# sensor.net
KiCad netlist of a schematic drawn in Altium Designer
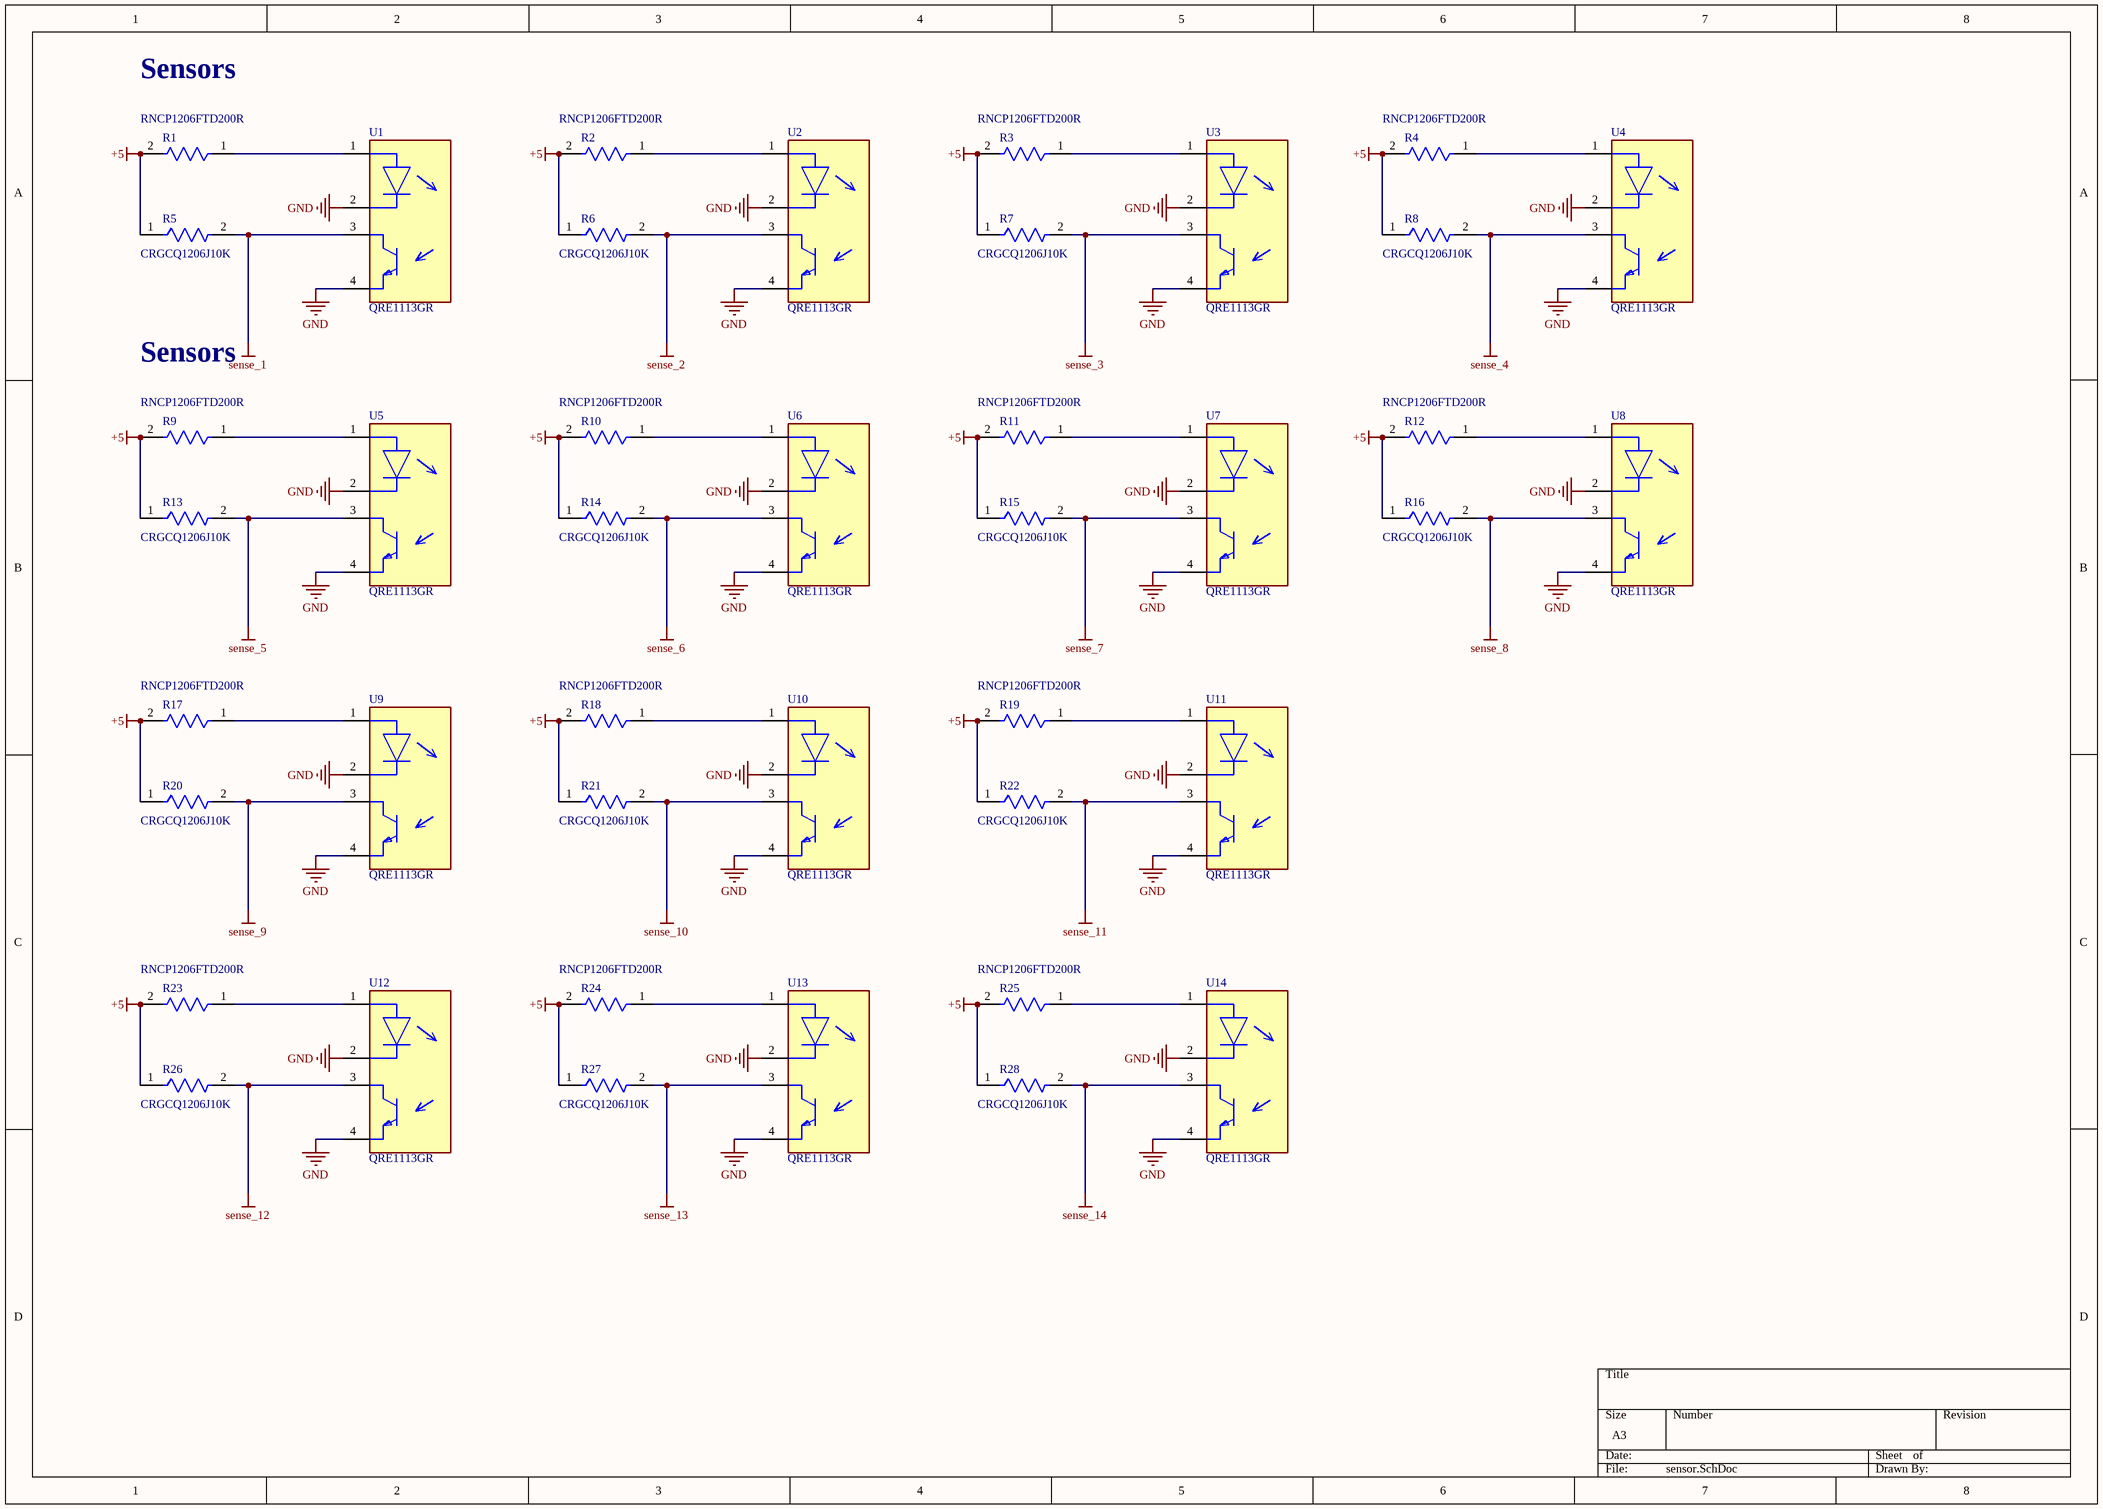
[diagram p0: sensor.SchDoc]

(export (version "E")
  (design (tool "Eeschema 10.0.6"))
  (components
    (comp (ref "R1")
      (value "RNCP1206FTD200R")
      (footprint "FP-RNCP1206-IPC_B")
      (description "200Ω ±1% 0.5W 1206 High Power Anti-Sulfur Thin Film Chip Resistor")
      (fields (field (name "TOLERANCE") "1%"))
      (libsource (lib "Altium Content Vault") (part "1029c3af85768c4190bb7ad29bc67b5"))
    )
    (comp (ref "R2")
      (value "RNCP1206FTD200R")
      (footprint "FP-RNCP1206-IPC_B")
      (description "200Ω ±1% 0.5W 1206 High Power Anti-Sulfur Thin Film Chip Resistor")
      (fields (field (name "TOLERANCE") "1%"))
      (libsource (lib "Altium Content Vault") (part "1029c3af85768c4190bb7ad29bc67b5"))
    )
    (comp (ref "R3")
      (value "RNCP1206FTD200R")
      (footprint "FP-RNCP1206-IPC_B")
      (description "200Ω ±1% 0.5W 1206 High Power Anti-Sulfur Thin Film Chip Resistor")
      (fields (field (name "TOLERANCE") "1%"))
      (libsource (lib "Altium Content Vault") (part "1029c3af85768c4190bb7ad29bc67b5"))
    )
    (comp (ref "R4")
      (value "RNCP1206FTD200R")
      (footprint "FP-RNCP1206-IPC_B")
      (description "200Ω ±1% 0.5W 1206 High Power Anti-Sulfur Thin Film Chip Resistor")
      (fields (field (name "TOLERANCE") "1%"))
      (libsource (lib "Altium Content Vault") (part "1029c3af85768c4190bb7ad29bc67b5"))
    )
    (comp (ref "R5")
      (value "CRGCQ1206J10K")
      (footprint "FP-CRGCQ1206-IPC_C")
      (description "CRGCQ1206 10KΩ 0.25W 5% ±100ppm/°C 200V")
      (fields (field (name "MANUFACTURER") "TE Connectivity") (field (name "TOLERANCE") "0.05"))
      (libsource (lib "Altium Content Vault") (part "1029c3af85768c4190bb7ad29bc67b5"))
    )
    (comp (ref "R6")
      (value "CRGCQ1206J10K")
      (footprint "FP-CRGCQ1206-IPC_C")
      (description "CRGCQ1206 10KΩ 0.25W 5% ±100ppm/°C 200V")
      (fields (field (name "MANUFACTURER") "TE Connectivity") (field (name "TOLERANCE") "0.05"))
      (libsource (lib "Altium Content Vault") (part "1029c3af85768c4190bb7ad29bc67b5"))
    )
    (comp (ref "R7")
      (value "CRGCQ1206J10K")
      (footprint "FP-CRGCQ1206-IPC_C")
      (description "CRGCQ1206 10KΩ 0.25W 5% ±100ppm/°C 200V")
      (fields (field (name "MANUFACTURER") "TE Connectivity") (field (name "TOLERANCE") "0.05"))
      (libsource (lib "Altium Content Vault") (part "1029c3af85768c4190bb7ad29bc67b5"))
    )
    (comp (ref "R8")
      (value "CRGCQ1206J10K")
      (footprint "FP-CRGCQ1206-IPC_C")
      (description "CRGCQ1206 10KΩ 0.25W 5% ±100ppm/°C 200V")
      (fields (field (name "MANUFACTURER") "TE Connectivity") (field (name "TOLERANCE") "0.05"))
      (libsource (lib "Altium Content Vault") (part "1029c3af85768c4190bb7ad29bc67b5"))
    )
    (comp (ref "R9")
      (value "RNCP1206FTD200R")
      (footprint "FP-RNCP1206-IPC_B")
      (description "200Ω ±1% 0.5W 1206 High Power Anti-Sulfur Thin Film Chip Resistor")
      (fields (field (name "TOLERANCE") "1%"))
      (libsource (lib "Altium Content Vault") (part "1029c3af85768c4190bb7ad29bc67b5"))
    )
    (comp (ref "R10")
      (value "RNCP1206FTD200R")
      (footprint "FP-RNCP1206-IPC_B")
      (description "200Ω ±1% 0.5W 1206 High Power Anti-Sulfur Thin Film Chip Resistor")
      (fields (field (name "TOLERANCE") "1%"))
      (libsource (lib "Altium Content Vault") (part "1029c3af85768c4190bb7ad29bc67b5"))
    )
    (comp (ref "R11")
      (value "RNCP1206FTD200R")
      (footprint "FP-RNCP1206-IPC_B")
      (description "200Ω ±1% 0.5W 1206 High Power Anti-Sulfur Thin Film Chip Resistor")
      (fields (field (name "TOLERANCE") "1%"))
      (libsource (lib "Altium Content Vault") (part "1029c3af85768c4190bb7ad29bc67b5"))
    )
    (comp (ref "R12")
      (value "RNCP1206FTD200R")
      (footprint "FP-RNCP1206-IPC_B")
      (description "200Ω ±1% 0.5W 1206 High Power Anti-Sulfur Thin Film Chip Resistor")
      (fields (field (name "TOLERANCE") "1%"))
      (libsource (lib "Altium Content Vault") (part "1029c3af85768c4190bb7ad29bc67b5"))
    )
    (comp (ref "R13")
      (value "CRGCQ1206J10K")
      (footprint "FP-CRGCQ1206-IPC_C")
      (description "CRGCQ1206 10KΩ 0.25W 5% ±100ppm/°C 200V")
      (fields (field (name "MANUFACTURER") "TE Connectivity") (field (name "TOLERANCE") "0.05"))
      (libsource (lib "Altium Content Vault") (part "1029c3af85768c4190bb7ad29bc67b5"))
    )
    (comp (ref "R14")
      (value "CRGCQ1206J10K")
      (footprint "FP-CRGCQ1206-IPC_C")
      (description "CRGCQ1206 10KΩ 0.25W 5% ±100ppm/°C 200V")
      (fields (field (name "MANUFACTURER") "TE Connectivity") (field (name "TOLERANCE") "0.05"))
      (libsource (lib "Altium Content Vault") (part "1029c3af85768c4190bb7ad29bc67b5"))
    )
    (comp (ref "R15")
      (value "CRGCQ1206J10K")
      (footprint "FP-CRGCQ1206-IPC_C")
      (description "CRGCQ1206 10KΩ 0.25W 5% ±100ppm/°C 200V")
      (fields (field (name "MANUFACTURER") "TE Connectivity") (field (name "TOLERANCE") "0.05"))
      (libsource (lib "Altium Content Vault") (part "1029c3af85768c4190bb7ad29bc67b5"))
    )
    (comp (ref "R16")
      (value "CRGCQ1206J10K")
      (footprint "FP-CRGCQ1206-IPC_C")
      (description "CRGCQ1206 10KΩ 0.25W 5% ±100ppm/°C 200V")
      (fields (field (name "MANUFACTURER") "TE Connectivity") (field (name "TOLERANCE") "0.05"))
      (libsource (lib "Altium Content Vault") (part "1029c3af85768c4190bb7ad29bc67b5"))
    )
    (comp (ref "R17")
      (value "RNCP1206FTD200R")
      (footprint "FP-RNCP1206-IPC_B")
      (description "200Ω ±1% 0.5W 1206 High Power Anti-Sulfur Thin Film Chip Resistor")
      (fields (field (name "TOLERANCE") "1%"))
      (libsource (lib "Altium Content Vault") (part "1029c3af85768c4190bb7ad29bc67b5"))
    )
    (comp (ref "R18")
      (value "RNCP1206FTD200R")
      (footprint "FP-RNCP1206-IPC_B")
      (description "200Ω ±1% 0.5W 1206 High Power Anti-Sulfur Thin Film Chip Resistor")
      (fields (field (name "TOLERANCE") "1%"))
      (libsource (lib "Altium Content Vault") (part "1029c3af85768c4190bb7ad29bc67b5"))
    )
    (comp (ref "R19")
      (value "RNCP1206FTD200R")
      (footprint "FP-RNCP1206-IPC_B")
      (description "200Ω ±1% 0.5W 1206 High Power Anti-Sulfur Thin Film Chip Resistor")
      (fields (field (name "TOLERANCE") "1%"))
      (libsource (lib "Altium Content Vault") (part "1029c3af85768c4190bb7ad29bc67b5"))
    )
    (comp (ref "R20")
      (value "CRGCQ1206J10K")
      (footprint "FP-CRGCQ1206-IPC_C")
      (description "CRGCQ1206 10KΩ 0.25W 5% ±100ppm/°C 200V")
      (fields (field (name "MANUFACTURER") "TE Connectivity") (field (name "TOLERANCE") "0.05"))
      (libsource (lib "Altium Content Vault") (part "1029c3af85768c4190bb7ad29bc67b5"))
    )
    (comp (ref "R21")
      (value "CRGCQ1206J10K")
      (footprint "FP-CRGCQ1206-IPC_C")
      (description "CRGCQ1206 10KΩ 0.25W 5% ±100ppm/°C 200V")
      (fields (field (name "MANUFACTURER") "TE Connectivity") (field (name "TOLERANCE") "0.05"))
      (libsource (lib "Altium Content Vault") (part "1029c3af85768c4190bb7ad29bc67b5"))
    )
    (comp (ref "R22")
      (value "CRGCQ1206J10K")
      (footprint "FP-CRGCQ1206-IPC_C")
      (description "CRGCQ1206 10KΩ 0.25W 5% ±100ppm/°C 200V")
      (fields (field (name "MANUFACTURER") "TE Connectivity") (field (name "TOLERANCE") "0.05"))
      (libsource (lib "Altium Content Vault") (part "1029c3af85768c4190bb7ad29bc67b5"))
    )
    (comp (ref "R23")
      (value "RNCP1206FTD200R")
      (footprint "FP-RNCP1206-IPC_B")
      (description "200Ω ±1% 0.5W 1206 High Power Anti-Sulfur Thin Film Chip Resistor")
      (fields (field (name "TOLERANCE") "1%"))
      (libsource (lib "Altium Content Vault") (part "1029c3af85768c4190bb7ad29bc67b5"))
    )
    (comp (ref "R24")
      (value "RNCP1206FTD200R")
      (footprint "FP-RNCP1206-IPC_B")
      (description "200Ω ±1% 0.5W 1206 High Power Anti-Sulfur Thin Film Chip Resistor")
      (fields (field (name "TOLERANCE") "1%"))
      (libsource (lib "Altium Content Vault") (part "1029c3af85768c4190bb7ad29bc67b5"))
    )
    (comp (ref "R25")
      (value "RNCP1206FTD200R")
      (footprint "FP-RNCP1206-IPC_B")
      (description "200Ω ±1% 0.5W 1206 High Power Anti-Sulfur Thin Film Chip Resistor")
      (fields (field (name "TOLERANCE") "1%"))
      (libsource (lib "Altium Content Vault") (part "1029c3af85768c4190bb7ad29bc67b5"))
    )
    (comp (ref "R26")
      (value "CRGCQ1206J10K")
      (footprint "FP-CRGCQ1206-IPC_C")
      (description "CRGCQ1206 10KΩ 0.25W 5% ±100ppm/°C 200V")
      (fields (field (name "MANUFACTURER") "TE Connectivity") (field (name "TOLERANCE") "0.05"))
      (libsource (lib "Altium Content Vault") (part "1029c3af85768c4190bb7ad29bc67b5"))
    )
    (comp (ref "R27")
      (value "CRGCQ1206J10K")
      (footprint "FP-CRGCQ1206-IPC_C")
      (description "CRGCQ1206 10KΩ 0.25W 5% ±100ppm/°C 200V")
      (fields (field (name "MANUFACTURER") "TE Connectivity") (field (name "TOLERANCE") "0.05"))
      (libsource (lib "Altium Content Vault") (part "1029c3af85768c4190bb7ad29bc67b5"))
    )
    (comp (ref "R28")
      (value "CRGCQ1206J10K")
      (footprint "FP-CRGCQ1206-IPC_C")
      (description "CRGCQ1206 10KΩ 0.25W 5% ±100ppm/°C 200V")
      (fields (field (name "MANUFACTURER") "TE Connectivity") (field (name "TOLERANCE") "0.05"))
      (libsource (lib "Altium Content Vault") (part "1029c3af85768c4190bb7ad29bc67b5"))
    )
    (comp (ref "U1")
      (value "QRE1113GR")
      (footprint "FP-100CY-MFG")
      (description "SENSOR OPTO TRANS REFL SMD PHOTO")
      (libsource (lib "Altium Content Vault") (part "7f7a55cf1778c7f4ea4f35509e0890d"))
    )
    (comp (ref "U2")
      (value "QRE1113GR")
      (footprint "FP-100CY-MFG")
      (description "SENSOR OPTO TRANS REFL SMD PHOTO")
      (libsource (lib "Altium Content Vault") (part "7f7a55cf1778c7f4ea4f35509e0890d"))
    )
    (comp (ref "U3")
      (value "QRE1113GR")
      (footprint "FP-100CY-MFG")
      (description "SENSOR OPTO TRANS REFL SMD PHOTO")
      (libsource (lib "Altium Content Vault") (part "7f7a55cf1778c7f4ea4f35509e0890d"))
    )
    (comp (ref "U4")
      (value "QRE1113GR")
      (footprint "FP-100CY-MFG")
      (description "SENSOR OPTO TRANS REFL SMD PHOTO")
      (libsource (lib "Altium Content Vault") (part "7f7a55cf1778c7f4ea4f35509e0890d"))
    )
    (comp (ref "U5")
      (value "QRE1113GR")
      (footprint "FP-100CY-MFG")
      (description "SENSOR OPTO TRANS REFL SMD PHOTO")
      (libsource (lib "Altium Content Vault") (part "7f7a55cf1778c7f4ea4f35509e0890d"))
    )
    (comp (ref "U6")
      (value "QRE1113GR")
      (footprint "FP-100CY-MFG")
      (description "SENSOR OPTO TRANS REFL SMD PHOTO")
      (libsource (lib "Altium Content Vault") (part "7f7a55cf1778c7f4ea4f35509e0890d"))
    )
    (comp (ref "U7")
      (value "QRE1113GR")
      (footprint "FP-100CY-MFG")
      (description "SENSOR OPTO TRANS REFL SMD PHOTO")
      (libsource (lib "Altium Content Vault") (part "7f7a55cf1778c7f4ea4f35509e0890d"))
    )
    (comp (ref "U8")
      (value "QRE1113GR")
      (footprint "FP-100CY-MFG")
      (description "SENSOR OPTO TRANS REFL SMD PHOTO")
      (libsource (lib "Altium Content Vault") (part "7f7a55cf1778c7f4ea4f35509e0890d"))
    )
    (comp (ref "U9")
      (value "QRE1113GR")
      (footprint "FP-100CY-MFG")
      (description "SENSOR OPTO TRANS REFL SMD PHOTO")
      (libsource (lib "Altium Content Vault") (part "7f7a55cf1778c7f4ea4f35509e0890d"))
    )
    (comp (ref "U10")
      (value "QRE1113GR")
      (footprint "FP-100CY-MFG")
      (description "SENSOR OPTO TRANS REFL SMD PHOTO")
      (libsource (lib "Altium Content Vault") (part "7f7a55cf1778c7f4ea4f35509e0890d"))
    )
    (comp (ref "U11")
      (value "QRE1113GR")
      (footprint "FP-100CY-MFG")
      (description "SENSOR OPTO TRANS REFL SMD PHOTO")
      (libsource (lib "Altium Content Vault") (part "7f7a55cf1778c7f4ea4f35509e0890d"))
    )
    (comp (ref "U12")
      (value "QRE1113GR")
      (footprint "FP-100CY-MFG")
      (description "SENSOR OPTO TRANS REFL SMD PHOTO")
      (libsource (lib "Altium Content Vault") (part "7f7a55cf1778c7f4ea4f35509e0890d"))
    )
    (comp (ref "U13")
      (value "QRE1113GR")
      (footprint "FP-100CY-MFG")
      (description "SENSOR OPTO TRANS REFL SMD PHOTO")
      (libsource (lib "Altium Content Vault") (part "7f7a55cf1778c7f4ea4f35509e0890d"))
    )
    (comp (ref "U14")
      (value "QRE1113GR")
      (footprint "FP-100CY-MFG")
      (description "SENSOR OPTO TRANS REFL SMD PHOTO")
      (libsource (lib "Altium Content Vault") (part "7f7a55cf1778c7f4ea4f35509e0890d"))
    )
  )
  (nets
    (net (code "1") (name "+5") (class "Default")
      (node (ref "R1") (pin "2") (pinfunction "2_2") (pintype "passive"))
      (node (ref "R10") (pin "2") (pinfunction "2_2") (pintype "passive"))
      (node (ref "R11") (pin "2") (pinfunction "2_2") (pintype "passive"))
      (node (ref "R12") (pin "2") (pinfunction "2_2") (pintype "passive"))
      (node (ref "R13") (pin "1") (pinfunction "1_1") (pintype "passive"))
      (node (ref "R14") (pin "1") (pinfunction "1_1") (pintype "passive"))
      (node (ref "R15") (pin "1") (pinfunction "1_1") (pintype "passive"))
      (node (ref "R16") (pin "1") (pinfunction "1_1") (pintype "passive"))
      (node (ref "R17") (pin "2") (pinfunction "2_2") (pintype "passive"))
      (node (ref "R18") (pin "2") (pinfunction "2_2") (pintype "passive"))
      (node (ref "R19") (pin "2") (pinfunction "2_2") (pintype "passive"))
      (node (ref "R2") (pin "2") (pinfunction "2_2") (pintype "passive"))
      (node (ref "R20") (pin "1") (pinfunction "1_1") (pintype "passive"))
      (node (ref "R21") (pin "1") (pinfunction "1_1") (pintype "passive"))
      (node (ref "R22") (pin "1") (pinfunction "1_1") (pintype "passive"))
      (node (ref "R23") (pin "2") (pinfunction "2_2") (pintype "passive"))
      (node (ref "R24") (pin "2") (pinfunction "2_2") (pintype "passive"))
      (node (ref "R25") (pin "2") (pinfunction "2_2") (pintype "passive"))
      (node (ref "R26") (pin "1") (pinfunction "1_1") (pintype "passive"))
      (node (ref "R27") (pin "1") (pinfunction "1_1") (pintype "passive"))
      (node (ref "R28") (pin "1") (pinfunction "1_1") (pintype "passive"))
      (node (ref "R3") (pin "2") (pinfunction "2_2") (pintype "passive"))
      (node (ref "R4") (pin "2") (pinfunction "2_2") (pintype "passive"))
      (node (ref "R5") (pin "1") (pinfunction "1_1") (pintype "passive"))
      (node (ref "R6") (pin "1") (pinfunction "1_1") (pintype "passive"))
      (node (ref "R7") (pin "1") (pinfunction "1_1") (pintype "passive"))
      (node (ref "R8") (pin "1") (pinfunction "1_1") (pintype "passive"))
      (node (ref "R9") (pin "2") (pinfunction "2_2") (pintype "passive"))
    )
    (net (code "2") (name "GND") (class "Default")
      (node (ref "U1") (pin "2") (pinfunction "C_2") (pintype "passive"))
      (node (ref "U1") (pin "4") (pinfunction "E_4") (pintype "passive"))
      (node (ref "U10") (pin "2") (pinfunction "C_2") (pintype "passive"))
      (node (ref "U10") (pin "4") (pinfunction "E_4") (pintype "passive"))
      (node (ref "U11") (pin "2") (pinfunction "C_2") (pintype "passive"))
      (node (ref "U11") (pin "4") (pinfunction "E_4") (pintype "passive"))
      (node (ref "U12") (pin "2") (pinfunction "C_2") (pintype "passive"))
      (node (ref "U12") (pin "4") (pinfunction "E_4") (pintype "passive"))
      (node (ref "U13") (pin "2") (pinfunction "C_2") (pintype "passive"))
      (node (ref "U13") (pin "4") (pinfunction "E_4") (pintype "passive"))
      (node (ref "U14") (pin "2") (pinfunction "C_2") (pintype "passive"))
      (node (ref "U14") (pin "4") (pinfunction "E_4") (pintype "passive"))
      (node (ref "U2") (pin "2") (pinfunction "C_2") (pintype "passive"))
      (node (ref "U2") (pin "4") (pinfunction "E_4") (pintype "passive"))
      (node (ref "U3") (pin "2") (pinfunction "C_2") (pintype "passive"))
      (node (ref "U3") (pin "4") (pinfunction "E_4") (pintype "passive"))
      (node (ref "U4") (pin "2") (pinfunction "C_2") (pintype "passive"))
      (node (ref "U4") (pin "4") (pinfunction "E_4") (pintype "passive"))
      (node (ref "U5") (pin "2") (pinfunction "C_2") (pintype "passive"))
      (node (ref "U5") (pin "4") (pinfunction "E_4") (pintype "passive"))
      (node (ref "U6") (pin "2") (pinfunction "C_2") (pintype "passive"))
      (node (ref "U6") (pin "4") (pinfunction "E_4") (pintype "passive"))
      (node (ref "U7") (pin "2") (pinfunction "C_2") (pintype "passive"))
      (node (ref "U7") (pin "4") (pinfunction "E_4") (pintype "passive"))
      (node (ref "U8") (pin "2") (pinfunction "C_2") (pintype "passive"))
      (node (ref "U8") (pin "4") (pinfunction "E_4") (pintype "passive"))
      (node (ref "U9") (pin "2") (pinfunction "C_2") (pintype "passive"))
      (node (ref "U9") (pin "4") (pinfunction "E_4") (pintype "passive"))
    )
    (net (code "3") (name "Net-(U1-A)") (class "Default")
      (node (ref "R1") (pin "1") (pinfunction "1_1") (pintype "passive"))
      (node (ref "U1") (pin "1") (pinfunction "A_1") (pintype "passive"))
    )
    (net (code "4") (name "Net-(U2-A)") (class "Default")
      (node (ref "R2") (pin "1") (pinfunction "1_1") (pintype "passive"))
      (node (ref "U2") (pin "1") (pinfunction "A_1") (pintype "passive"))
    )
    (net (code "5") (name "Net-(U3-A)") (class "Default")
      (node (ref "R3") (pin "1") (pinfunction "1_1") (pintype "passive"))
      (node (ref "U3") (pin "1") (pinfunction "A_1") (pintype "passive"))
    )
    (net (code "6") (name "Net-(U4-A)") (class "Default")
      (node (ref "R4") (pin "1") (pinfunction "1_1") (pintype "passive"))
      (node (ref "U4") (pin "1") (pinfunction "A_1") (pintype "passive"))
    )
    (net (code "7") (name "Net-(U5-A)") (class "Default")
      (node (ref "R9") (pin "1") (pinfunction "1_1") (pintype "passive"))
      (node (ref "U5") (pin "1") (pinfunction "A_1") (pintype "passive"))
    )
    (net (code "8") (name "Net-(U6-A)") (class "Default")
      (node (ref "R10") (pin "1") (pinfunction "1_1") (pintype "passive"))
      (node (ref "U6") (pin "1") (pinfunction "A_1") (pintype "passive"))
    )
    (net (code "9") (name "Net-(U7-A)") (class "Default")
      (node (ref "R11") (pin "1") (pinfunction "1_1") (pintype "passive"))
      (node (ref "U7") (pin "1") (pinfunction "A_1") (pintype "passive"))
    )
    (net (code "10") (name "Net-(U8-A)") (class "Default")
      (node (ref "R12") (pin "1") (pinfunction "1_1") (pintype "passive"))
      (node (ref "U8") (pin "1") (pinfunction "A_1") (pintype "passive"))
    )
    (net (code "11") (name "Net-(U9-A)") (class "Default")
      (node (ref "R17") (pin "1") (pinfunction "1_1") (pintype "passive"))
      (node (ref "U9") (pin "1") (pinfunction "A_1") (pintype "passive"))
    )
    (net (code "12") (name "Net-(U10-A)") (class "Default")
      (node (ref "R18") (pin "1") (pinfunction "1_1") (pintype "passive"))
      (node (ref "U10") (pin "1") (pinfunction "A_1") (pintype "passive"))
    )
    (net (code "13") (name "Net-(U11-A)") (class "Default")
      (node (ref "R19") (pin "1") (pinfunction "1_1") (pintype "passive"))
      (node (ref "U11") (pin "1") (pinfunction "A_1") (pintype "passive"))
    )
    (net (code "14") (name "Net-(U12-A)") (class "Default")
      (node (ref "R23") (pin "1") (pinfunction "1_1") (pintype "passive"))
      (node (ref "U12") (pin "1") (pinfunction "A_1") (pintype "passive"))
    )
    (net (code "15") (name "Net-(U13-A)") (class "Default")
      (node (ref "R24") (pin "1") (pinfunction "1_1") (pintype "passive"))
      (node (ref "U13") (pin "1") (pinfunction "A_1") (pintype "passive"))
    )
    (net (code "16") (name "Net-(U14-A)") (class "Default")
      (node (ref "R25") (pin "1") (pinfunction "1_1") (pintype "passive"))
      (node (ref "U14") (pin "1") (pinfunction "A_1") (pintype "passive"))
    )
    (net (code "17") (name "sense_1") (class "Default")
      (node (ref "R5") (pin "2") (pinfunction "2_2") (pintype "passive"))
      (node (ref "U1") (pin "3") (pinfunction "C_3") (pintype "passive"))
    )
    (net (code "18") (name "sense_2") (class "Default")
      (node (ref "R6") (pin "2") (pinfunction "2_2") (pintype "passive"))
      (node (ref "U2") (pin "3") (pinfunction "C_3") (pintype "passive"))
    )
    (net (code "19") (name "sense_3") (class "Default")
      (node (ref "R7") (pin "2") (pinfunction "2_2") (pintype "passive"))
      (node (ref "U3") (pin "3") (pinfunction "C_3") (pintype "passive"))
    )
    (net (code "20") (name "sense_4") (class "Default")
      (node (ref "R8") (pin "2") (pinfunction "2_2") (pintype "passive"))
      (node (ref "U4") (pin "3") (pinfunction "C_3") (pintype "passive"))
    )
    (net (code "21") (name "sense_5") (class "Default")
      (node (ref "R13") (pin "2") (pinfunction "2_2") (pintype "passive"))
      (node (ref "U5") (pin "3") (pinfunction "C_3") (pintype "passive"))
    )
    (net (code "22") (name "sense_6") (class "Default")
      (node (ref "R14") (pin "2") (pinfunction "2_2") (pintype "passive"))
      (node (ref "U6") (pin "3") (pinfunction "C_3") (pintype "passive"))
    )
    (net (code "23") (name "sense_7") (class "Default")
      (node (ref "R15") (pin "2") (pinfunction "2_2") (pintype "passive"))
      (node (ref "U7") (pin "3") (pinfunction "C_3") (pintype "passive"))
    )
    (net (code "24") (name "sense_8") (class "Default")
      (node (ref "R16") (pin "2") (pinfunction "2_2") (pintype "passive"))
      (node (ref "U8") (pin "3") (pinfunction "C_3") (pintype "passive"))
    )
    (net (code "25") (name "sense_9") (class "Default")
      (node (ref "R20") (pin "2") (pinfunction "2_2") (pintype "passive"))
      (node (ref "U9") (pin "3") (pinfunction "C_3") (pintype "passive"))
    )
    (net (code "26") (name "sense_10") (class "Default")
      (node (ref "R21") (pin "2") (pinfunction "2_2") (pintype "passive"))
      (node (ref "U10") (pin "3") (pinfunction "C_3") (pintype "passive"))
    )
    (net (code "27") (name "sense_11") (class "Default")
      (node (ref "R22") (pin "2") (pinfunction "2_2") (pintype "passive"))
      (node (ref "U11") (pin "3") (pinfunction "C_3") (pintype "passive"))
    )
    (net (code "28") (name "sense_12") (class "Default")
      (node (ref "R26") (pin "2") (pinfunction "2_2") (pintype "passive"))
      (node (ref "U12") (pin "3") (pinfunction "C_3") (pintype "passive"))
    )
    (net (code "29") (name "sense_13") (class "Default")
      (node (ref "R27") (pin "2") (pinfunction "2_2") (pintype "passive"))
      (node (ref "U13") (pin "3") (pinfunction "C_3") (pintype "passive"))
    )
    (net (code "30") (name "sense_14") (class "Default")
      (node (ref "R28") (pin "2") (pinfunction "2_2") (pintype "passive"))
      (node (ref "U14") (pin "3") (pinfunction "C_3") (pintype "passive"))
    )
  )
)
